# driver.net
KiCad netlist of a schematic drawn in EAGLE
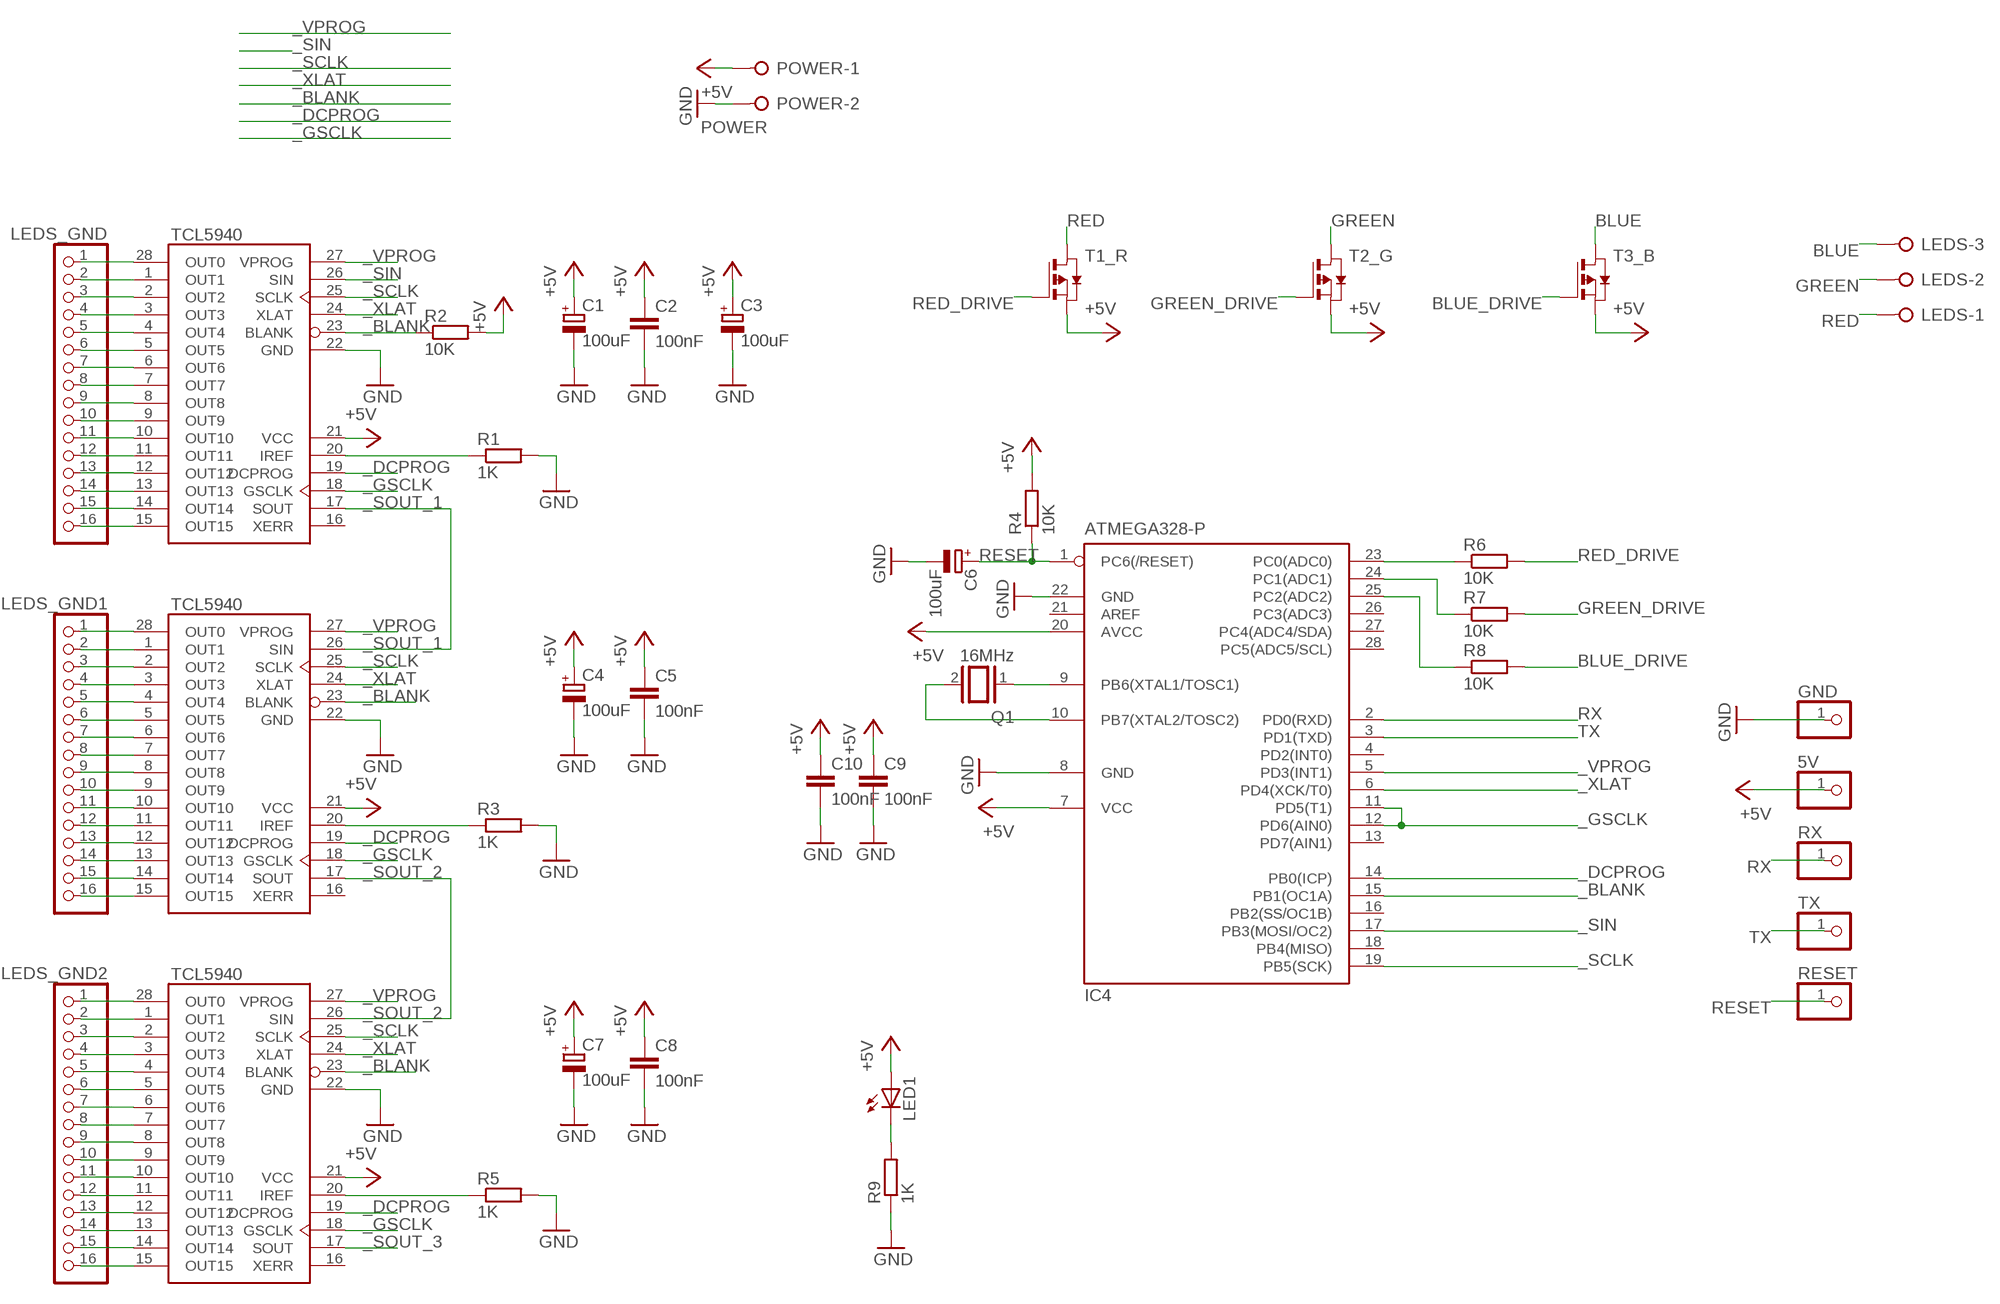
[diagram p0: schematic, sheet 1]

(export (version "E")
  (design (tool "Eeschema 10.0.6"))
  (components
    (comp (ref "5V")
      (value "PINHD-1X1")
      (footprint "eagle-import:1X01")
      (libsource (lib "eagle-import") (part "PINHD-1X1"))
    )
    (comp (ref "C1")
      (value "100uF")
      (footprint "eagle-import:E2,5-6")
      (libsource (lib "eagle-import") (part "CPOL-EUE2.5-6"))
    )
    (comp (ref "C2")
      (value "100nF")
      (footprint "eagle-import:C025-025X050")
      (libsource (lib "eagle-import") (part "C-EU025-025X050"))
    )
    (comp (ref "C3")
      (value "100uF")
      (footprint "eagle-import:E2,5-6")
      (libsource (lib "eagle-import") (part "CPOL-EUE2.5-6"))
    )
    (comp (ref "C4")
      (value "100uF")
      (footprint "eagle-import:E2,5-6")
      (libsource (lib "eagle-import") (part "CPOL-EUE2.5-6"))
    )
    (comp (ref "C5")
      (value "100nF")
      (footprint "eagle-import:C025-025X050")
      (libsource (lib "eagle-import") (part "C-EU025-025X050"))
    )
    (comp (ref "C6")
      (value "100uF")
      (footprint "eagle-import:E2,5-6")
      (libsource (lib "eagle-import") (part "CPOL-EUE2.5-6"))
    )
    (comp (ref "C7")
      (value "100uF")
      (footprint "eagle-import:E2,5-6")
      (libsource (lib "eagle-import") (part "CPOL-EUE2.5-6"))
    )
    (comp (ref "C8")
      (value "100nF")
      (footprint "eagle-import:C025-025X050")
      (libsource (lib "eagle-import") (part "C-EU025-025X050"))
    )
    (comp (ref "C9")
      (value "100nF")
      (footprint "eagle-import:C025-025X050")
      (libsource (lib "eagle-import") (part "C-EU025-025X050"))
    )
    (comp (ref "C10")
      (value "100nF")
      (footprint "eagle-import:C025-025X050")
      (libsource (lib "eagle-import") (part "C-EU025-025X050"))
    )
    (comp (ref "GND")
      (value "PINHD-1X1")
      (footprint "eagle-import:1X01")
      (libsource (lib "eagle-import") (part "PINHD-1X1"))
    )
    (comp (ref "IC4")
      (value "ATMEGA328-P")
      (footprint "eagle-import:DIL28-3")
      (libsource (lib "eagle-import") (part "MEGA8-P"))
    )
    (comp (ref "LED1")
      (value "LED5MM")
      (footprint "eagle-import:LED5MM")
      (libsource (lib "eagle-import") (part "LED5MM"))
    )
    (comp (ref "LEDS")
      (value "W237-3E")
      (footprint "eagle-import:W237-3E")
      (libsource (lib "eagle-import") (part "W237-3E"))
    )
    (comp (ref "LEDS_GND")
      (value "PINHD-1X16")
      (footprint "eagle-import:1X16")
      (libsource (lib "eagle-import") (part "PINHD-1X16"))
    )
    (comp (ref "LEDS_GND1")
      (value "PINHD-1X16")
      (footprint "eagle-import:1X16")
      (libsource (lib "eagle-import") (part "PINHD-1X16"))
    )
    (comp (ref "LEDS_GND2")
      (value "PINHD-1X16")
      (footprint "eagle-import:1X16")
      (libsource (lib "eagle-import") (part "PINHD-1X16"))
    )
    (comp (ref "POWER")
      (value "POWER")
      (footprint "eagle-import:W237-132")
      (libsource (lib "eagle-import") (part "W237-02P"))
    )
    (comp (ref "Q1")
      (value "16MHz")
      (footprint "eagle-import:QS")
      (libsource (lib "eagle-import") (part "XTAL/S"))
    )
    (comp (ref "R1")
      (value "1K")
      (footprint "eagle-import:M0805")
      (libsource (lib "eagle-import") (part "R-EU_M0805"))
    )
    (comp (ref "R2")
      (value "10K")
      (footprint "eagle-import:M0805")
      (libsource (lib "eagle-import") (part "R-EU_M0805"))
    )
    (comp (ref "R3")
      (value "1K")
      (footprint "eagle-import:M0805")
      (libsource (lib "eagle-import") (part "R-EU_M0805"))
    )
    (comp (ref "R4")
      (value "10K")
      (footprint "eagle-import:M0805")
      (libsource (lib "eagle-import") (part "R-EU_M0805"))
    )
    (comp (ref "R5")
      (value "1K")
      (footprint "eagle-import:M0805")
      (libsource (lib "eagle-import") (part "R-EU_M0805"))
    )
    (comp (ref "R6")
      (value "10K")
      (footprint "eagle-import:M0805")
      (libsource (lib "eagle-import") (part "R-EU_M0805"))
    )
    (comp (ref "R7")
      (value "10K")
      (footprint "eagle-import:M0805")
      (libsource (lib "eagle-import") (part "R-EU_M0805"))
    )
    (comp (ref "R8")
      (value "10K")
      (footprint "eagle-import:M0805")
      (libsource (lib "eagle-import") (part "R-EU_M0805"))
    )
    (comp (ref "R9")
      (value "1K")
      (footprint "eagle-import:M0805")
      (libsource (lib "eagle-import") (part "R-EU_M0805"))
    )
    (comp (ref "RESET")
      (value "PINHD-1X1")
      (footprint "eagle-import:1X01")
      (libsource (lib "eagle-import") (part "PINHD-1X1"))
    )
    (comp (ref "RX")
      (value "PINHD-1X1")
      (footprint "eagle-import:1X01")
      (libsource (lib "eagle-import") (part "PINHD-1X1"))
    )
    (comp (ref "T1_R")
      (value "PMOSSOT23")
      (footprint "eagle-import:SOT-23")
      (libsource (lib "eagle-import") (part "PMOSSOT23"))
    )
    (comp (ref "T2_G")
      (value "PMOSSOT23")
      (footprint "eagle-import:SOT-23")
      (libsource (lib "eagle-import") (part "PMOSSOT23"))
    )
    (comp (ref "T3_B")
      (value "PMOSSOT23")
      (footprint "eagle-import:SOT-23")
      (libsource (lib "eagle-import") (part "PMOSSOT23"))
    )
    (comp (ref "TCL5940_1")
      (value "TCL5940")
      (footprint "eagle-import:DIP28")
      (libsource (lib "eagle-import") (part "TCL5940"))
    )
    (comp (ref "TLC5940_2")
      (value "TCL5940")
      (footprint "eagle-import:DIP28")
      (libsource (lib "eagle-import") (part "TCL5940"))
    )
    (comp (ref "TLC5940_3")
      (value "TCL5940")
      (footprint "eagle-import:DIP28")
      (libsource (lib "eagle-import") (part "TCL5940"))
    )
    (comp (ref "TX")
      (value "PINHD-1X1")
      (footprint "eagle-import:1X01")
      (libsource (lib "eagle-import") (part "PINHD-1X1"))
    )
  )
  (nets
    (net (code "1") (name "+5V") (class "Default")
      (node (ref "5V") (pin "1") (pinfunction "1_1") (pintype "passive"))
      (node (ref "C1") (pin "+") (pinfunction "+_+") (pintype "passive"))
      (node (ref "C10") (pin "1") (pinfunction "1_1") (pintype "passive"))
      (node (ref "C2") (pin "1") (pinfunction "1_1") (pintype "passive"))
      (node (ref "C3") (pin "+") (pinfunction "+_+") (pintype "passive"))
      (node (ref "C4") (pin "+") (pinfunction "+_+") (pintype "passive"))
      (node (ref "C5") (pin "1") (pinfunction "1_1") (pintype "passive"))
      (node (ref "C7") (pin "+") (pinfunction "+_+") (pintype "passive"))
      (node (ref "C8") (pin "1") (pinfunction "1_1") (pintype "passive"))
      (node (ref "C9") (pin "1") (pinfunction "1_1") (pintype "passive"))
      (node (ref "IC4") (pin "20") (pinfunction "AVCC_20") (pintype "power_in"))
      (node (ref "IC4") (pin "7") (pinfunction "VCC_7") (pintype "power_in"))
      (node (ref "LED1") (pin "A") (pinfunction "A_A") (pintype "passive"))
      (node (ref "POWER") (pin "1") (pinfunction "KL_1") (pintype "passive"))
      (node (ref "R2") (pin "2") (pinfunction "2_2") (pintype "passive"))
      (node (ref "R4") (pin "2") (pinfunction "2_2") (pintype "passive"))
      (node (ref "T1_R") (pin "2") (pinfunction "S_2") (pintype "passive"))
      (node (ref "T2_G") (pin "2") (pinfunction "S_2") (pintype "passive"))
      (node (ref "T3_B") (pin "2") (pinfunction "S_2") (pintype "passive"))
      (node (ref "TCL5940_1") (pin "21") (pinfunction "VCC_21") (pintype "power_in"))
      (node (ref "TLC5940_2") (pin "21") (pinfunction "VCC_21") (pintype "power_in"))
      (node (ref "TLC5940_3") (pin "21") (pinfunction "VCC_21") (pintype "power_in"))
    )
    (net (code "2") (name "/BLUE") (class "Default")
      (node (ref "LEDS") (pin "3") (pinfunction "KL_3") (pintype "passive"))
      (node (ref "T3_B") (pin "1") (pinfunction "D_1") (pintype "passive"))
    )
    (net (code "3") (name "/BLUE_DRIVE") (class "Default")
      (node (ref "R8") (pin "2") (pinfunction "2_2") (pintype "passive"))
      (node (ref "T3_B") (pin "3") (pinfunction "G_3") (pintype "passive"))
    )
    (net (code "4") (name "/GREEN") (class "Default")
      (node (ref "LEDS") (pin "2") (pinfunction "KL_2") (pintype "passive"))
      (node (ref "T2_G") (pin "1") (pinfunction "D_1") (pintype "passive"))
    )
    (net (code "5") (name "/GREEN_DRIVE") (class "Default")
      (node (ref "R7") (pin "2") (pinfunction "2_2") (pintype "passive"))
      (node (ref "T2_G") (pin "3") (pinfunction "G_3") (pintype "passive"))
    )
    (net (code "6") (name "/RED") (class "Default")
      (node (ref "LEDS") (pin "1") (pinfunction "KL_1") (pintype "passive"))
      (node (ref "T1_R") (pin "1") (pinfunction "D_1") (pintype "passive"))
    )
    (net (code "7") (name "/RED_DRIVE") (class "Default")
      (node (ref "R6") (pin "2") (pinfunction "2_2") (pintype "passive"))
      (node (ref "T1_R") (pin "3") (pinfunction "G_3") (pintype "passive"))
    )
    (net (code "8") (name "/RESET") (class "Default")
      (node (ref "C6") (pin "+") (pinfunction "+_+") (pintype "passive"))
      (node (ref "IC4") (pin "1") (pinfunction "PC6(/RESET)_1") (pintype "bidirectional"))
      (node (ref "R4") (pin "1") (pinfunction "1_1") (pintype "passive"))
      (node (ref "RESET") (pin "1") (pinfunction "1_1") (pintype "passive"))
    )
    (net (code "9") (name "/RX") (class "Default")
      (node (ref "IC4") (pin "2") (pinfunction "PD0(RXD)_2") (pintype "bidirectional"))
      (node (ref "RX") (pin "1") (pinfunction "1_1") (pintype "passive"))
    )
    (net (code "10") (name "/TX") (class "Default")
      (node (ref "IC4") (pin "3") (pinfunction "PD1(TXD)_3") (pintype "bidirectional"))
      (node (ref "TX") (pin "1") (pinfunction "1_1") (pintype "passive"))
    )
    (net (code "11") (name "/_BLANK") (class "Default")
      (node (ref "IC4") (pin "15") (pinfunction "PB1(OC1A)_15") (pintype "bidirectional"))
      (node (ref "R2") (pin "1") (pinfunction "1_1") (pintype "passive"))
      (node (ref "TCL5940_1") (pin "23") (pinfunction "BLANK_23") (pintype "input"))
      (node (ref "TLC5940_2") (pin "23") (pinfunction "BLANK_23") (pintype "input"))
      (node (ref "TLC5940_3") (pin "23") (pinfunction "BLANK_23") (pintype "input"))
    )
    (net (code "12") (name "/_DCPROG") (class "Default")
      (node (ref "IC4") (pin "14") (pinfunction "PB0(ICP)_14") (pintype "bidirectional"))
      (node (ref "TCL5940_1") (pin "19") (pinfunction "DCPROG_19") (pintype "input"))
      (node (ref "TLC5940_2") (pin "19") (pinfunction "DCPROG_19") (pintype "input"))
      (node (ref "TLC5940_3") (pin "19") (pinfunction "DCPROG_19") (pintype "input"))
    )
    (net (code "13") (name "/_GSCLK") (class "Default")
      (node (ref "IC4") (pin "11") (pinfunction "PD5(T1)_11") (pintype "bidirectional"))
      (node (ref "IC4") (pin "12") (pinfunction "PD6(AIN0)_12") (pintype "bidirectional"))
      (node (ref "TCL5940_1") (pin "18") (pinfunction "GSCLK_18") (pintype "input"))
      (node (ref "TLC5940_2") (pin "18") (pinfunction "GSCLK_18") (pintype "input"))
      (node (ref "TLC5940_3") (pin "18") (pinfunction "GSCLK_18") (pintype "input"))
    )
    (net (code "14") (name "/_SCLK") (class "Default")
      (node (ref "IC4") (pin "19") (pinfunction "PB5(SCK)_19") (pintype "bidirectional"))
      (node (ref "TCL5940_1") (pin "25") (pinfunction "SCLK_25") (pintype "input"))
      (node (ref "TLC5940_2") (pin "25") (pinfunction "SCLK_25") (pintype "input"))
      (node (ref "TLC5940_3") (pin "25") (pinfunction "SCLK_25") (pintype "input"))
    )
    (net (code "15") (name "/_SIN") (class "Default")
      (node (ref "IC4") (pin "17") (pinfunction "PB3(MOSI/OC2)_17") (pintype "bidirectional"))
      (node (ref "TCL5940_1") (pin "26") (pinfunction "SIN_26") (pintype "input"))
    )
    (net (code "16") (name "/_SOUT_1") (class "Default")
      (node (ref "TCL5940_1") (pin "17") (pinfunction "SOUT_17") (pintype "output"))
      (node (ref "TLC5940_2") (pin "26") (pinfunction "SIN_26") (pintype "input"))
    )
    (net (code "17") (name "/_SOUT_2") (class "Default")
      (node (ref "TLC5940_2") (pin "17") (pinfunction "SOUT_17") (pintype "output"))
      (node (ref "TLC5940_3") (pin "26") (pinfunction "SIN_26") (pintype "input"))
    )
    (net (code "18") (name "/_SOUT_3") (class "Default")
      (node (ref "TLC5940_3") (pin "17") (pinfunction "SOUT_17") (pintype "output"))
    )
    (net (code "19") (name "/_VPROG") (class "Default")
      (node (ref "IC4") (pin "5") (pinfunction "PD3(INT1)_5") (pintype "bidirectional"))
      (node (ref "TCL5940_1") (pin "27") (pinfunction "VPROG_27") (pintype "bidirectional"))
      (node (ref "TLC5940_2") (pin "27") (pinfunction "VPROG_27") (pintype "bidirectional"))
      (node (ref "TLC5940_3") (pin "27") (pinfunction "VPROG_27") (pintype "bidirectional"))
    )
    (net (code "20") (name "/_XLAT") (class "Default")
      (node (ref "IC4") (pin "6") (pinfunction "PD4(XCK/T0)_6") (pintype "bidirectional"))
      (node (ref "TCL5940_1") (pin "24") (pinfunction "XLAT_24") (pintype "input"))
      (node (ref "TLC5940_2") (pin "24") (pinfunction "XLAT_24") (pintype "input"))
      (node (ref "TLC5940_3") (pin "24") (pinfunction "XLAT_24") (pintype "input"))
    )
    (net (code "21") (name "GND") (class "Default")
      (node (ref "C1") (pin "-") (pinfunction "-_-") (pintype "passive"))
      (node (ref "C10") (pin "2") (pinfunction "2_2") (pintype "passive"))
      (node (ref "C2") (pin "2") (pinfunction "2_2") (pintype "passive"))
      (node (ref "C3") (pin "-") (pinfunction "-_-") (pintype "passive"))
      (node (ref "C4") (pin "-") (pinfunction "-_-") (pintype "passive"))
      (node (ref "C5") (pin "2") (pinfunction "2_2") (pintype "passive"))
      (node (ref "C6") (pin "-") (pinfunction "-_-") (pintype "passive"))
      (node (ref "C7") (pin "-") (pinfunction "-_-") (pintype "passive"))
      (node (ref "C8") (pin "2") (pinfunction "2_2") (pintype "passive"))
      (node (ref "C9") (pin "2") (pinfunction "2_2") (pintype "passive"))
      (node (ref "GND") (pin "1") (pinfunction "1_1") (pintype "passive"))
      (node (ref "IC4") (pin "22") (pinfunction "GND_22") (pintype "power_in"))
      (node (ref "IC4") (pin "8") (pinfunction "GND_8") (pintype "power_in"))
      (node (ref "POWER") (pin "2") (pinfunction "KL_2") (pintype "passive"))
      (node (ref "R1") (pin "2") (pinfunction "2_2") (pintype "passive"))
      (node (ref "R3") (pin "2") (pinfunction "2_2") (pintype "passive"))
      (node (ref "R5") (pin "2") (pinfunction "2_2") (pintype "passive"))
      (node (ref "R9") (pin "1") (pinfunction "1_1") (pintype "passive"))
      (node (ref "TCL5940_1") (pin "22") (pinfunction "GND_22") (pintype "power_in"))
      (node (ref "TLC5940_2") (pin "22") (pinfunction "GND_22") (pintype "power_in"))
      (node (ref "TLC5940_3") (pin "22") (pinfunction "GND_22") (pintype "power_in"))
    )
    (net (code "22") (name "Net-(IC4-PB6(XTAL1{slash}TOSC1))") (class "Default")
      (node (ref "IC4") (pin "9") (pinfunction "PB6(XTAL1/TOSC1)_9") (pintype "bidirectional"))
      (node (ref "Q1") (pin "1") (pinfunction "1_1") (pintype "passive"))
    )
    (net (code "23") (name "Net-(IC4-PB7(XTAL2{slash}TOSC2))") (class "Default")
      (node (ref "IC4") (pin "10") (pinfunction "PB7(XTAL2/TOSC2)_10") (pintype "bidirectional"))
      (node (ref "Q1") (pin "2") (pinfunction "2_2") (pintype "passive"))
    )
    (net (code "24") (name "Net-(IC4-PC0(ADC0))") (class "Default")
      (node (ref "IC4") (pin "23") (pinfunction "PC0(ADC0)_23") (pintype "bidirectional"))
      (node (ref "R6") (pin "1") (pinfunction "1_1") (pintype "passive"))
    )
    (net (code "25") (name "Net-(IC4-PC1(ADC1))") (class "Default")
      (node (ref "IC4") (pin "24") (pinfunction "PC1(ADC1)_24") (pintype "bidirectional"))
      (node (ref "R7") (pin "1") (pinfunction "1_1") (pintype "passive"))
    )
    (net (code "26") (name "Net-(IC4-PC2(ADC2))") (class "Default")
      (node (ref "IC4") (pin "25") (pinfunction "PC2(ADC2)_25") (pintype "bidirectional"))
      (node (ref "R8") (pin "1") (pinfunction "1_1") (pintype "passive"))
    )
    (net (code "27") (name "Net-(LED1-C)") (class "Default")
      (node (ref "LED1") (pin "K") (pinfunction "C_K") (pintype "passive"))
      (node (ref "R9") (pin "2") (pinfunction "2_2") (pintype "passive"))
    )
    (net (code "28") (name "Net-(TCL5940_1-IREF)") (class "Default")
      (node (ref "R1") (pin "1") (pinfunction "1_1") (pintype "passive"))
      (node (ref "TCL5940_1") (pin "20") (pinfunction "IREF_20") (pintype "input"))
    )
    (net (code "29") (name "Net-(TCL5940_1-OUT0)") (class "Default")
      (node (ref "LEDS_GND") (pin "1") (pinfunction "1_1") (pintype "passive"))
      (node (ref "TCL5940_1") (pin "28") (pinfunction "OUT0_28") (pintype "output"))
    )
    (net (code "30") (name "Net-(TCL5940_1-OUT1)") (class "Default")
      (node (ref "LEDS_GND") (pin "2") (pinfunction "2_2") (pintype "passive"))
      (node (ref "TCL5940_1") (pin "1") (pinfunction "OUT1_1") (pintype "output"))
    )
    (net (code "31") (name "Net-(TCL5940_1-OUT2)") (class "Default")
      (node (ref "LEDS_GND") (pin "3") (pinfunction "3_3") (pintype "passive"))
      (node (ref "TCL5940_1") (pin "2") (pinfunction "OUT2_2") (pintype "output"))
    )
    (net (code "32") (name "Net-(TCL5940_1-OUT3)") (class "Default")
      (node (ref "LEDS_GND") (pin "4") (pinfunction "4_4") (pintype "passive"))
      (node (ref "TCL5940_1") (pin "3") (pinfunction "OUT3_3") (pintype "output"))
    )
    (net (code "33") (name "Net-(TCL5940_1-OUT4)") (class "Default")
      (node (ref "LEDS_GND") (pin "5") (pinfunction "5_5") (pintype "passive"))
      (node (ref "TCL5940_1") (pin "4") (pinfunction "OUT4_4") (pintype "output"))
    )
    (net (code "34") (name "Net-(TCL5940_1-OUT5)") (class "Default")
      (node (ref "LEDS_GND") (pin "6") (pinfunction "6_6") (pintype "passive"))
      (node (ref "TCL5940_1") (pin "5") (pinfunction "OUT5_5") (pintype "output"))
    )
    (net (code "35") (name "Net-(TCL5940_1-OUT6)") (class "Default")
      (node (ref "LEDS_GND") (pin "7") (pinfunction "7_7") (pintype "passive"))
      (node (ref "TCL5940_1") (pin "6") (pinfunction "OUT6_6") (pintype "output"))
    )
    (net (code "36") (name "Net-(TCL5940_1-OUT7)") (class "Default")
      (node (ref "LEDS_GND") (pin "8") (pinfunction "8_8") (pintype "passive"))
      (node (ref "TCL5940_1") (pin "7") (pinfunction "OUT7_7") (pintype "output"))
    )
    (net (code "37") (name "Net-(TCL5940_1-OUT8)") (class "Default")
      (node (ref "LEDS_GND") (pin "9") (pinfunction "9_9") (pintype "passive"))
      (node (ref "TCL5940_1") (pin "8") (pinfunction "OUT8_8") (pintype "output"))
    )
    (net (code "38") (name "Net-(TCL5940_1-OUT9)") (class "Default")
      (node (ref "LEDS_GND") (pin "10") (pinfunction "10_10") (pintype "passive"))
      (node (ref "TCL5940_1") (pin "9") (pinfunction "OUT9_9") (pintype "output"))
    )
    (net (code "39") (name "Net-(TCL5940_1-OUT10)") (class "Default")
      (node (ref "LEDS_GND") (pin "11") (pinfunction "11_11") (pintype "passive"))
      (node (ref "TCL5940_1") (pin "10") (pinfunction "OUT10_10") (pintype "output"))
    )
    (net (code "40") (name "Net-(TCL5940_1-OUT11)") (class "Default")
      (node (ref "LEDS_GND") (pin "12") (pinfunction "12_12") (pintype "passive"))
      (node (ref "TCL5940_1") (pin "11") (pinfunction "OUT11_11") (pintype "output"))
    )
    (net (code "41") (name "Net-(TCL5940_1-OUT12)") (class "Default")
      (node (ref "LEDS_GND") (pin "13") (pinfunction "13_13") (pintype "passive"))
      (node (ref "TCL5940_1") (pin "12") (pinfunction "OUT12_12") (pintype "output"))
    )
    (net (code "42") (name "Net-(TCL5940_1-OUT13)") (class "Default")
      (node (ref "LEDS_GND") (pin "14") (pinfunction "14_14") (pintype "passive"))
      (node (ref "TCL5940_1") (pin "13") (pinfunction "OUT13_13") (pintype "output"))
    )
    (net (code "43") (name "Net-(TCL5940_1-OUT14)") (class "Default")
      (node (ref "LEDS_GND") (pin "15") (pinfunction "15_15") (pintype "passive"))
      (node (ref "TCL5940_1") (pin "14") (pinfunction "OUT14_14") (pintype "output"))
    )
    (net (code "44") (name "Net-(TCL5940_1-OUT15)") (class "Default")
      (node (ref "LEDS_GND") (pin "16") (pinfunction "16_16") (pintype "passive"))
      (node (ref "TCL5940_1") (pin "15") (pinfunction "OUT15_15") (pintype "output"))
    )
    (net (code "45") (name "Net-(TLC5940_2-IREF)") (class "Default")
      (node (ref "R3") (pin "1") (pinfunction "1_1") (pintype "passive"))
      (node (ref "TLC5940_2") (pin "20") (pinfunction "IREF_20") (pintype "input"))
    )
    (net (code "46") (name "Net-(TLC5940_2-OUT0)") (class "Default")
      (node (ref "LEDS_GND1") (pin "1") (pinfunction "1_1") (pintype "passive"))
      (node (ref "TLC5940_2") (pin "28") (pinfunction "OUT0_28") (pintype "output"))
    )
    (net (code "47") (name "Net-(TLC5940_2-OUT1)") (class "Default")
      (node (ref "LEDS_GND1") (pin "2") (pinfunction "2_2") (pintype "passive"))
      (node (ref "TLC5940_2") (pin "1") (pinfunction "OUT1_1") (pintype "output"))
    )
    (net (code "48") (name "Net-(TLC5940_2-OUT2)") (class "Default")
      (node (ref "LEDS_GND1") (pin "3") (pinfunction "3_3") (pintype "passive"))
      (node (ref "TLC5940_2") (pin "2") (pinfunction "OUT2_2") (pintype "output"))
    )
    (net (code "49") (name "Net-(TLC5940_2-OUT3)") (class "Default")
      (node (ref "LEDS_GND1") (pin "4") (pinfunction "4_4") (pintype "passive"))
      (node (ref "TLC5940_2") (pin "3") (pinfunction "OUT3_3") (pintype "output"))
    )
    (net (code "50") (name "Net-(TLC5940_2-OUT4)") (class "Default")
      (node (ref "LEDS_GND1") (pin "5") (pinfunction "5_5") (pintype "passive"))
      (node (ref "TLC5940_2") (pin "4") (pinfunction "OUT4_4") (pintype "output"))
    )
    (net (code "51") (name "Net-(TLC5940_2-OUT5)") (class "Default")
      (node (ref "LEDS_GND1") (pin "6") (pinfunction "6_6") (pintype "passive"))
      (node (ref "TLC5940_2") (pin "5") (pinfunction "OUT5_5") (pintype "output"))
    )
    (net (code "52") (name "Net-(TLC5940_2-OUT6)") (class "Default")
      (node (ref "LEDS_GND1") (pin "7") (pinfunction "7_7") (pintype "passive"))
      (node (ref "TLC5940_2") (pin "6") (pinfunction "OUT6_6") (pintype "output"))
    )
    (net (code "53") (name "Net-(TLC5940_2-OUT7)") (class "Default")
      (node (ref "LEDS_GND1") (pin "8") (pinfunction "8_8") (pintype "passive"))
      (node (ref "TLC5940_2") (pin "7") (pinfunction "OUT7_7") (pintype "output"))
    )
    (net (code "54") (name "Net-(TLC5940_2-OUT8)") (class "Default")
      (node (ref "LEDS_GND1") (pin "9") (pinfunction "9_9") (pintype "passive"))
      (node (ref "TLC5940_2") (pin "8") (pinfunction "OUT8_8") (pintype "output"))
    )
    (net (code "55") (name "Net-(TLC5940_2-OUT9)") (class "Default")
      (node (ref "LEDS_GND1") (pin "10") (pinfunction "10_10") (pintype "passive"))
      (node (ref "TLC5940_2") (pin "9") (pinfunction "OUT9_9") (pintype "output"))
    )
    (net (code "56") (name "Net-(TLC5940_2-OUT10)") (class "Default")
      (node (ref "LEDS_GND1") (pin "11") (pinfunction "11_11") (pintype "passive"))
      (node (ref "TLC5940_2") (pin "10") (pinfunction "OUT10_10") (pintype "output"))
    )
    (net (code "57") (name "Net-(TLC5940_2-OUT11)") (class "Default")
      (node (ref "LEDS_GND1") (pin "12") (pinfunction "12_12") (pintype "passive"))
      (node (ref "TLC5940_2") (pin "11") (pinfunction "OUT11_11") (pintype "output"))
    )
    (net (code "58") (name "Net-(TLC5940_2-OUT12)") (class "Default")
      (node (ref "LEDS_GND1") (pin "13") (pinfunction "13_13") (pintype "passive"))
      (node (ref "TLC5940_2") (pin "12") (pinfunction "OUT12_12") (pintype "output"))
    )
    (net (code "59") (name "Net-(TLC5940_2-OUT13)") (class "Default")
      (node (ref "LEDS_GND1") (pin "14") (pinfunction "14_14") (pintype "passive"))
      (node (ref "TLC5940_2") (pin "13") (pinfunction "OUT13_13") (pintype "output"))
    )
    (net (code "60") (name "Net-(TLC5940_2-OUT14)") (class "Default")
      (node (ref "LEDS_GND1") (pin "15") (pinfunction "15_15") (pintype "passive"))
      (node (ref "TLC5940_2") (pin "14") (pinfunction "OUT14_14") (pintype "output"))
    )
    (net (code "61") (name "Net-(TLC5940_2-OUT15)") (class "Default")
      (node (ref "LEDS_GND1") (pin "16") (pinfunction "16_16") (pintype "passive"))
      (node (ref "TLC5940_2") (pin "15") (pinfunction "OUT15_15") (pintype "output"))
    )
    (net (code "62") (name "Net-(TLC5940_3-IREF)") (class "Default")
      (node (ref "R5") (pin "1") (pinfunction "1_1") (pintype "passive"))
      (node (ref "TLC5940_3") (pin "20") (pinfunction "IREF_20") (pintype "input"))
    )
    (net (code "63") (name "Net-(TLC5940_3-OUT0)") (class "Default")
      (node (ref "LEDS_GND2") (pin "1") (pinfunction "1_1") (pintype "passive"))
      (node (ref "TLC5940_3") (pin "28") (pinfunction "OUT0_28") (pintype "output"))
    )
    (net (code "64") (name "Net-(TLC5940_3-OUT1)") (class "Default")
      (node (ref "LEDS_GND2") (pin "2") (pinfunction "2_2") (pintype "passive"))
      (node (ref "TLC5940_3") (pin "1") (pinfunction "OUT1_1") (pintype "output"))
    )
    (net (code "65") (name "Net-(TLC5940_3-OUT2)") (class "Default")
      (node (ref "LEDS_GND2") (pin "3") (pinfunction "3_3") (pintype "passive"))
      (node (ref "TLC5940_3") (pin "2") (pinfunction "OUT2_2") (pintype "output"))
    )
    (net (code "66") (name "Net-(TLC5940_3-OUT3)") (class "Default")
      (node (ref "LEDS_GND2") (pin "4") (pinfunction "4_4") (pintype "passive"))
      (node (ref "TLC5940_3") (pin "3") (pinfunction "OUT3_3") (pintype "output"))
    )
    (net (code "67") (name "Net-(TLC5940_3-OUT4)") (class "Default")
      (node (ref "LEDS_GND2") (pin "5") (pinfunction "5_5") (pintype "passive"))
      (node (ref "TLC5940_3") (pin "4") (pinfunction "OUT4_4") (pintype "output"))
    )
    (net (code "68") (name "Net-(TLC5940_3-OUT5)") (class "Default")
      (node (ref "LEDS_GND2") (pin "6") (pinfunction "6_6") (pintype "passive"))
      (node (ref "TLC5940_3") (pin "5") (pinfunction "OUT5_5") (pintype "output"))
    )
    (net (code "69") (name "Net-(TLC5940_3-OUT6)") (class "Default")
      (node (ref "LEDS_GND2") (pin "7") (pinfunction "7_7") (pintype "passive"))
      (node (ref "TLC5940_3") (pin "6") (pinfunction "OUT6_6") (pintype "output"))
    )
    (net (code "70") (name "Net-(TLC5940_3-OUT7)") (class "Default")
      (node (ref "LEDS_GND2") (pin "8") (pinfunction "8_8") (pintype "passive"))
      (node (ref "TLC5940_3") (pin "7") (pinfunction "OUT7_7") (pintype "output"))
    )
    (net (code "71") (name "Net-(TLC5940_3-OUT8)") (class "Default")
      (node (ref "LEDS_GND2") (pin "9") (pinfunction "9_9") (pintype "passive"))
      (node (ref "TLC5940_3") (pin "8") (pinfunction "OUT8_8") (pintype "output"))
    )
    (net (code "72") (name "Net-(TLC5940_3-OUT9)") (class "Default")
      (node (ref "LEDS_GND2") (pin "10") (pinfunction "10_10") (pintype "passive"))
      (node (ref "TLC5940_3") (pin "9") (pinfunction "OUT9_9") (pintype "output"))
    )
    (net (code "73") (name "Net-(TLC5940_3-OUT10)") (class "Default")
      (node (ref "LEDS_GND2") (pin "11") (pinfunction "11_11") (pintype "passive"))
      (node (ref "TLC5940_3") (pin "10") (pinfunction "OUT10_10") (pintype "output"))
    )
    (net (code "74") (name "Net-(TLC5940_3-OUT11)") (class "Default")
      (node (ref "LEDS_GND2") (pin "12") (pinfunction "12_12") (pintype "passive"))
      (node (ref "TLC5940_3") (pin "11") (pinfunction "OUT11_11") (pintype "output"))
    )
    (net (code "75") (name "Net-(TLC5940_3-OUT12)") (class "Default")
      (node (ref "LEDS_GND2") (pin "13") (pinfunction "13_13") (pintype "passive"))
      (node (ref "TLC5940_3") (pin "12") (pinfunction "OUT12_12") (pintype "output"))
    )
    (net (code "76") (name "Net-(TLC5940_3-OUT13)") (class "Default")
      (node (ref "LEDS_GND2") (pin "14") (pinfunction "14_14") (pintype "passive"))
      (node (ref "TLC5940_3") (pin "13") (pinfunction "OUT13_13") (pintype "output"))
    )
    (net (code "77") (name "Net-(TLC5940_3-OUT14)") (class "Default")
      (node (ref "LEDS_GND2") (pin "15") (pinfunction "15_15") (pintype "passive"))
      (node (ref "TLC5940_3") (pin "14") (pinfunction "OUT14_14") (pintype "output"))
    )
    (net (code "78") (name "Net-(TLC5940_3-OUT15)") (class "Default")
      (node (ref "LEDS_GND2") (pin "16") (pinfunction "16_16") (pintype "passive"))
      (node (ref "TLC5940_3") (pin "15") (pinfunction "OUT15_15") (pintype "output"))
    )
    (net (code "79") (name "unconnected-(IC4-AREF-Pad21)") (class "Default")
      (node (ref "IC4") (pin "21") (pinfunction "AREF_21") (pintype "passive"))
    )
    (net (code "80") (name "unconnected-(IC4-PB2(SS{slash}OC1B)-Pad16)") (class "Default")
      (node (ref "IC4") (pin "16") (pinfunction "PB2(SS/OC1B)_16") (pintype "bidirectional"))
    )
    (net (code "81") (name "unconnected-(IC4-PB4(MISO)-Pad18)") (class "Default")
      (node (ref "IC4") (pin "18") (pinfunction "PB4(MISO)_18") (pintype "bidirectional"))
    )
    (net (code "82") (name "unconnected-(IC4-PC3(ADC3)-Pad26)") (class "Default")
      (node (ref "IC4") (pin "26") (pinfunction "PC3(ADC3)_26") (pintype "bidirectional"))
    )
    (net (code "83") (name "unconnected-(IC4-PC4(ADC4{slash}SDA)-Pad27)") (class "Default")
      (node (ref "IC4") (pin "27") (pinfunction "PC4(ADC4/SDA)_27") (pintype "bidirectional"))
    )
    (net (code "84") (name "unconnected-(IC4-PC5(ADC5{slash}SCL)-Pad28)") (class "Default")
      (node (ref "IC4") (pin "28") (pinfunction "PC5(ADC5/SCL)_28") (pintype "bidirectional"))
    )
    (net (code "85") (name "unconnected-(IC4-PD2(INT0)-Pad4)") (class "Default")
      (node (ref "IC4") (pin "4") (pinfunction "PD2(INT0)_4") (pintype "bidirectional"))
    )
    (net (code "86") (name "unconnected-(IC4-PD7(AIN1)-Pad13)") (class "Default")
      (node (ref "IC4") (pin "13") (pinfunction "PD7(AIN1)_13") (pintype "bidirectional"))
    )
    (net (code "87") (name "unconnected-(TCL5940_1-XERR-Pad16)") (class "Default")
      (node (ref "TCL5940_1") (pin "16") (pinfunction "XERR_16") (pintype "output"))
    )
    (net (code "88") (name "unconnected-(TLC5940_2-XERR-Pad16)") (class "Default")
      (node (ref "TLC5940_2") (pin "16") (pinfunction "XERR_16") (pintype "output"))
    )
    (net (code "89") (name "unconnected-(TLC5940_3-XERR-Pad16)") (class "Default")
      (node (ref "TLC5940_3") (pin "16") (pinfunction "XERR_16") (pintype "output"))
    )
  )
)
